# Gumstix_Overo.net
KiCad netlist of a schematic drawn in Altium Designer
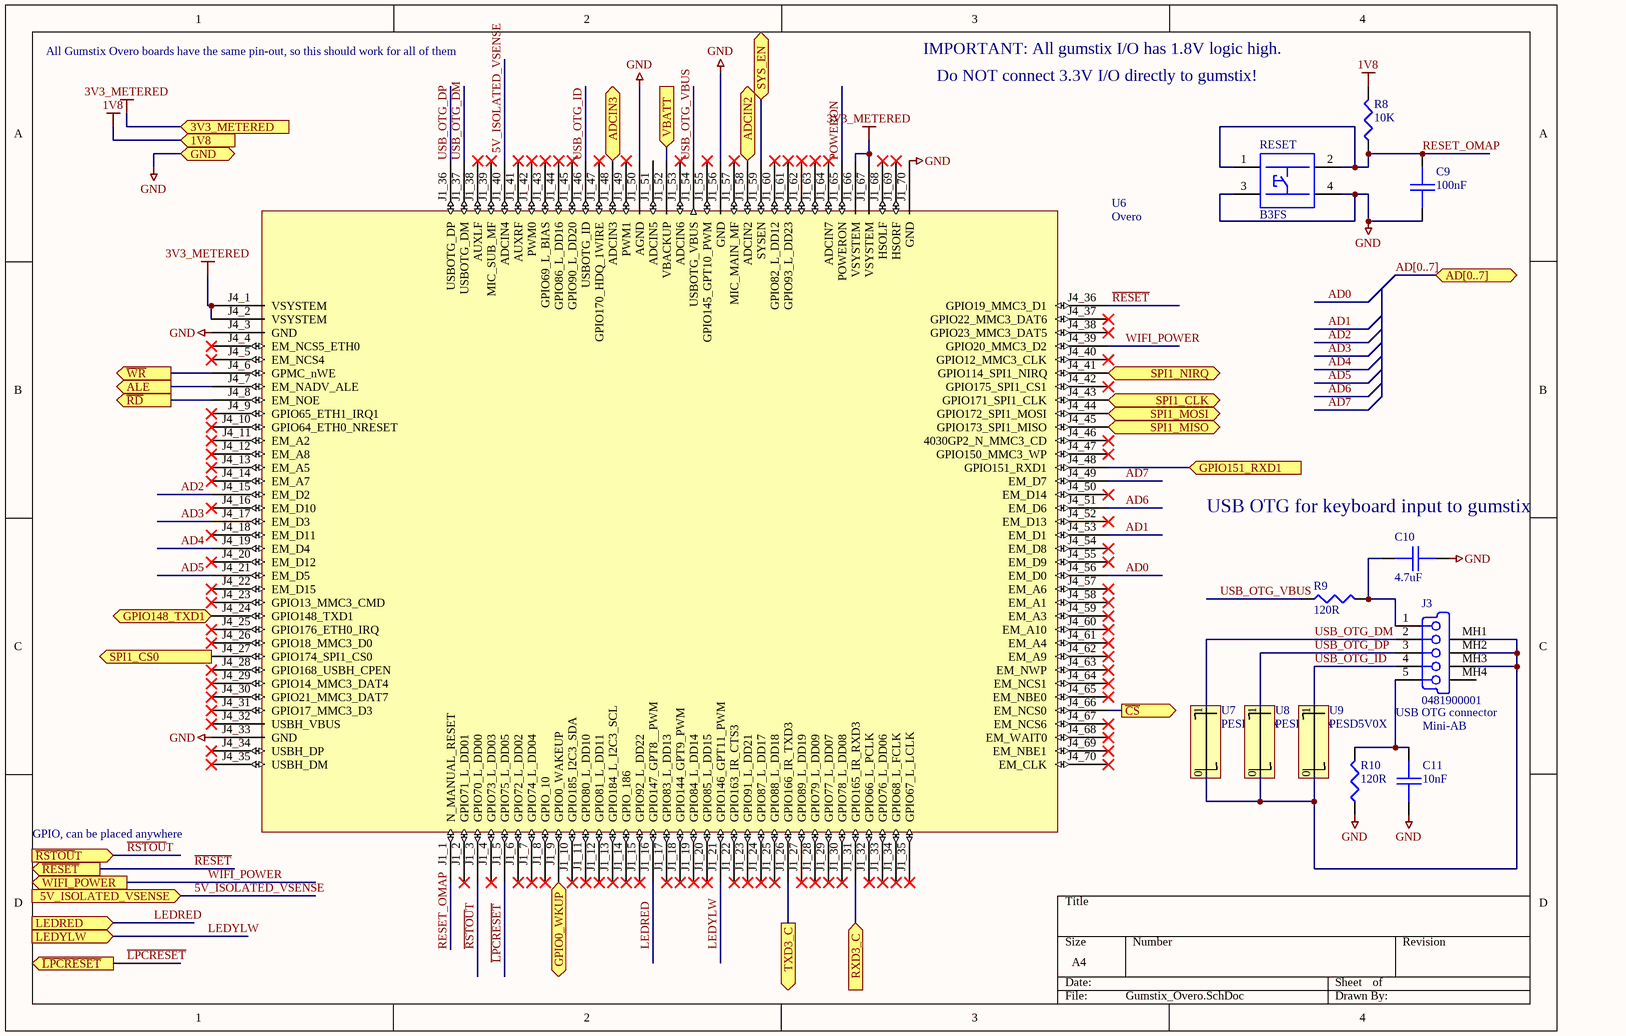
[diagram p0: Gumstix_Overo.SchDoc]

(export (version "E")
  (design (tool "Eeschema 10.0.6"))
  (components
    (comp (ref "C9")
      (value "100nF")
      (footprint "0603")
      (description "Capacitor")
      (libsource (lib "RCLDQ") (part "CAP"))
    )
    (comp (ref "C10")
      (value "4.7uF")
      (footprint "0603")
      (description "Capacitor")
      (libsource (lib "RCLDQ") (part "CAP"))
    )
    (comp (ref "C11")
      (value "10nF")
      (footprint "0603")
      (description "Capacitor")
      (libsource (lib "RCLDQ") (part "CAP"))
    )
    (comp (ref "J3")
      (value "0481900001")
      (footprint "MINI_USB_Molex")
      (fields (field (name "PUBLISHER") "Altium Limited"))
      (libsource (lib "Molex Serial Bus Mini USB") (part "0481900001"))
    )
    (comp (ref "R8")
      (value "10K")
      (footprint "0603")
      (description "Resistor")
      (libsource (lib "RCLDQ") (part "RES1"))
    )
    (comp (ref "R9")
      (value "120R")
      (footprint "0603")
      (description "Resistor")
      (libsource (lib "RCLDQ") (part "RES1"))
    )
    (comp (ref "R10")
      (value "120R")
      (footprint "0603")
      (description "Resistor")
      (libsource (lib "RCLDQ") (part "RES1"))
    )
    (comp (ref "RESET")
      (value "B3FS")
      (footprint "B3FS-1052")
      (description "SMD tactile switch")
      (libsource (lib "Miscellaneous") (part "B3FS"))
    )
    (comp (ref "U6")
      (value "Overo")
      (footprint "Overo-bare")
      (description "Gumstix Overo Motherboard")
      (libsource (lib "gumstix") (part "Overo"))
    )
    (comp (ref "U7")
      (value "PESD5V0X")
      (footprint "SOD323")
      (description "Ultra low capacitance bidirectional ESD protection diodes")
      (libsource (lib "gumstix") (part "PESD5V0X"))
    )
    (comp (ref "U8")
      (value "PESD5V0X")
      (footprint "SOD323")
      (description "Ultra low capacitance bidirectional ESD protection diodes")
      (libsource (lib "gumstix") (part "PESD5V0X"))
    )
    (comp (ref "U9")
      (value "PESD5V0X")
      (footprint "SOD323")
      (description "Ultra low capacitance bidirectional ESD protection diodes")
      (libsource (lib "gumstix") (part "PESD5V0X"))
    )
  )
  (nets
    (net (code "1") (name "/5V_ISOLATED_VSENSE") (class "Default")
      (node (ref "U6") (pin "J1_40") (pinfunction "ADCIN4_J1_40") (pintype "bidirectional"))
    )
    (net (code "2") (name "/AD0") (class "Default")
      (node (ref "U6") (pin "J4_56") (pinfunction "EM_D0_J4_56") (pintype "bidirectional"))
    )
    (net (code "3") (name "/AD1") (class "Default")
      (node (ref "U6") (pin "J4_53") (pinfunction "EM_D1_J4_53") (pintype "bidirectional"))
    )
    (net (code "4") (name "/AD2") (class "Default")
      (node (ref "U6") (pin "J4_15") (pinfunction "EM_D2_J4_15") (pintype "bidirectional"))
    )
    (net (code "5") (name "/AD3") (class "Default")
      (node (ref "U6") (pin "J4_17") (pinfunction "EM_D3_J4_17") (pintype "bidirectional"))
    )
    (net (code "6") (name "/AD4") (class "Default")
      (node (ref "U6") (pin "J4_19") (pinfunction "EM_D4_J4_19") (pintype "bidirectional"))
    )
    (net (code "7") (name "/AD5") (class "Default")
      (node (ref "U6") (pin "J4_21") (pinfunction "EM_D5_J4_21") (pintype "bidirectional"))
    )
    (net (code "8") (name "/AD6") (class "Default")
      (node (ref "U6") (pin "J4_51") (pinfunction "EM_D6_J4_51") (pintype "bidirectional"))
    )
    (net (code "9") (name "/AD7") (class "Default")
      (node (ref "U6") (pin "J4_49") (pinfunction "EM_D7_J4_49") (pintype "bidirectional"))
    )
    (net (code "10") (name "/ADCIN2") (class "Default")
      (node (ref "U6") (pin "J1_58") (pinfunction "ADCIN2_J1_58") (pintype "bidirectional"))
    )
    (net (code "11") (name "/ADCIN3") (class "Default")
      (node (ref "U6") (pin "J1_48") (pinfunction "ADCIN3_J1_48") (pintype "bidirectional"))
    )
    (net (code "13") (name "/ALE") (class "Default")
      (node (ref "U6") (pin "J4_7") (pinfunction "EM_NADV_ALE_J4_7") (pintype "bidirectional"))
    )
    (net (code "14") (name "/GPIO0_WKUP") (class "Default")
      (node (ref "U6") (pin "J1_9") (pinfunction "GPIO0_WAKEUP_J1_9") (pintype "bidirectional"))
    )
    (net (code "15") (name "/GPIO148_TXD1") (class "Default")
      (node (ref "U6") (pin "J4_24") (pinfunction "GPIO148_TXD1_J4_24") (pintype "bidirectional"))
    )
    (net (code "16") (name "/GPIO151_RXD1") (class "Default")
      (node (ref "U6") (pin "J4_48") (pinfunction "GPIO151_RXD1_J4_48") (pintype "bidirectional"))
    )
    (net (code "17") (name "/LEDRED") (class "Default")
      (node (ref "U6") (pin "J1_16") (pinfunction "GPIO147_GPT8__PWM_J1_16") (pintype "bidirectional"))
    )
    (net (code "18") (name "/LEDYLW") (class "Default")
      (node (ref "U6") (pin "J1_21") (pinfunction "GPIO146_GPT11_PWM_J1_21") (pintype "bidirectional"))
    )
    (net (code "19") (name "/POWERON") (class "Default")
      (node (ref "U6") (pin "J1_65") (pinfunction "POWERON_J1_65") (pintype "bidirectional"))
    )
    (net (code "20") (name "/RESET_OMAP") (class "Default")
      (node (ref "C9") (pin "1") (pinfunction "1_1") (pintype "passive"))
      (node (ref "R8") (pin "1") (pinfunction "1_1") (pintype "passive"))
      (node (ref "RESET") (pin "1") (pinfunction "A1_1") (pintype "passive"))
      (node (ref "RESET") (pin "2") (pinfunction "A2_2") (pintype "passive"))
      (node (ref "U6") (pin "J1_1") (pinfunction "N_MANUAL_RESET_J1_1") (pintype "bidirectional"))
    )
    (net (code "21") (name "/RXD3_C") (class "Default")
      (node (ref "U6") (pin "J1_31") (pinfunction "GPIO165_IR_RXD3_J1_31") (pintype "bidirectional"))
    )
    (net (code "22") (name "/SPI1_CLK") (class "Default")
      (node (ref "U6") (pin "J4_43") (pinfunction "GPIO171_SPI1_CLK_J4_43") (pintype "bidirectional"))
    )
    (net (code "23") (name "/SPI1_CS0") (class "Default")
      (node (ref "U6") (pin "J4_27") (pinfunction "GPIO174_SPI1_CS0_J4_27") (pintype "bidirectional"))
    )
    (net (code "24") (name "/SPI1_MISO") (class "Default")
      (node (ref "U6") (pin "J4_45") (pinfunction "GPIO173_SPI1_MISO_J4_45") (pintype "bidirectional"))
    )
    (net (code "25") (name "/SPI1_MOSI") (class "Default")
      (node (ref "U6") (pin "J4_44") (pinfunction "GPIO172_SPI1_MOSI_J4_44") (pintype "bidirectional"))
    )
    (net (code "26") (name "/SPI1_NIRQ") (class "Default")
      (node (ref "U6") (pin "J4_41") (pinfunction "GPIO114_SPI1_NIRQ_J4_41") (pintype "bidirectional"))
    )
    (net (code "27") (name "/SYS_EN") (class "Default")
      (node (ref "U6") (pin "J1_59") (pinfunction "SYSEN_J1_59") (pintype "bidirectional"))
    )
    (net (code "28") (name "/TXD3_C") (class "Default")
      (node (ref "U6") (pin "J1_26") (pinfunction "GPIO166_IR_TXD3_J1_26") (pintype "bidirectional"))
    )
    (net (code "29") (name "/USB_OTG_DM") (class "Default")
      (node (ref "J3") (pin "2") (pinfunction "D-_2") (pintype "passive"))
      (node (ref "U6") (pin "J1_37") (pinfunction "USBOTG_DM_J1_37") (pintype "bidirectional"))
      (node (ref "U7") (pin "1") (pintype "passive"))
    )
    (net (code "30") (name "/USB_OTG_DP") (class "Default")
      (node (ref "J3") (pin "3") (pinfunction "D+_3") (pintype "passive"))
      (node (ref "U6") (pin "J1_36") (pinfunction "USBOTG_DP_J1_36") (pintype "bidirectional"))
      (node (ref "U8") (pin "1") (pintype "passive"))
    )
    (net (code "31") (name "/USB_OTG_ID") (class "Default")
      (node (ref "J3") (pin "4") (pinfunction "NC_4") (pintype "passive"))
      (node (ref "U6") (pin "J1_46") (pinfunction "USBOTG_ID_J1_46") (pintype "bidirectional"))
      (node (ref "U9") (pin "1") (pintype "passive"))
    )
    (net (code "32") (name "/USB_OTG_VBUS") (class "Default")
      (node (ref "R9") (pin "1") (pinfunction "1_1") (pintype "passive"))
      (node (ref "U6") (pin "J1_54") (pinfunction "USBOTG_VBUS_J1_54") (pintype "output"))
    )
    (net (code "33") (name "/VBATT") (class "Default")
      (node (ref "U6") (pin "J1_52") (pinfunction "VBACKUP_J1_52") (pintype "power_in"))
    )
    (net (code "34") (name "/WIFI_POWER") (class "Default")
      (node (ref "U6") (pin "J4_39") (pinfunction "GPIO20_MMC3_D2_J4_39") (pintype "bidirectional"))
    )
    (net (code "35") (name "/~{CS}") (class "Default")
      (node (ref "U6") (pin "J4_66") (pinfunction "EM_NCS0_J4_66") (pintype "bidirectional"))
    )
    (net (code "36") (name "/~{LPCRESET}") (class "Default")
      (node (ref "U6") (pin "J1_5") (pinfunction "GPIO75_L_DD05_J1_5") (pintype "bidirectional"))
    )
    (net (code "37") (name "/~{RD}") (class "Default")
      (node (ref "U6") (pin "J4_8") (pinfunction "EM_NOE_J4_8") (pintype "bidirectional"))
    )
    (net (code "38") (name "/~{RESET}") (class "Default")
      (node (ref "U6") (pin "J4_36") (pinfunction "GPIO19_MMC3_D1_J4_36") (pintype "bidirectional"))
    )
    (net (code "39") (name "/~{RSTOU}T") (class "Default")
      (node (ref "U6") (pin "J1_3") (pinfunction "GPIO70_L_DD00_J1_3") (pintype "bidirectional"))
    )
    (net (code "40") (name "/~{WR}") (class "Default")
      (node (ref "U6") (pin "J4_6") (pinfunction "GPMC_nWE_J4_6") (pintype "bidirectional"))
    )
    (net (code "41") (name "1V8") (class "Default")
      (node (ref "R8") (pin "2") (pinfunction "2_2") (pintype "passive"))
    )
    (net (code "42") (name "3V3_METERED") (class "Default")
      (node (ref "U6") (pin "J1_66") (pinfunction "VSYSTEM_J1_66") (pintype "power_in"))
      (node (ref "U6") (pin "J1_67") (pinfunction "VSYSTEM_J1_67") (pintype "power_in"))
      (node (ref "U6") (pin "J4_1") (pinfunction "VSYSTEM_J4_1") (pintype "power_in"))
      (node (ref "U6") (pin "J4_2") (pinfunction "VSYSTEM_J4_2") (pintype "power_in"))
    )
    (net (code "43") (name "GND") (class "Default")
      (node (ref "C10") (pin "2") (pinfunction "2_2") (pintype "passive"))
      (node (ref "C11") (pin "2") (pinfunction "2_2") (pintype "passive"))
      (node (ref "C9") (pin "2") (pinfunction "2_2") (pintype "passive"))
      (node (ref "R10") (pin "1") (pinfunction "1_1") (pintype "passive"))
      (node (ref "RESET") (pin "3") (pinfunction "B2_3") (pintype "passive"))
      (node (ref "RESET") (pin "4") (pinfunction "B1_4") (pintype "passive"))
      (node (ref "U6") (pin "J1_50") (pinfunction "AGND_J1_50") (pintype "power_in"))
      (node (ref "U6") (pin "J1_56") (pinfunction "GND_J1_56") (pintype "power_in"))
      (node (ref "U6") (pin "J1_70") (pinfunction "GND_J1_70") (pintype "power_in"))
      (node (ref "U6") (pin "J4_3") (pinfunction "GND_J4_3") (pintype "power_in"))
      (node (ref "U6") (pin "J4_33") (pinfunction "GND_J4_33") (pintype "power_in"))
    )
    (net (code "44") (name "Net-(J3-GND)") (class "Default")
      (node (ref "C11") (pin "1") (pinfunction "1_1") (pintype "passive"))
      (node (ref "J3") (pin "5") (pinfunction "GND_5") (pintype "passive"))
      (node (ref "R10") (pin "2") (pinfunction "2_2") (pintype "passive"))
    )
    (net (code "45") (name "Net-(J3-Tab-PadMH1)") (class "Default")
      (node (ref "J3") (pin "MH1") (pinfunction "Tab_MH1") (pintype "passive"))
      (node (ref "J3") (pin "MH2") (pinfunction "Tab_MH2") (pintype "passive"))
      (node (ref "J3") (pin "MH3") (pinfunction "Tab_MH3") (pintype "passive"))
      (node (ref "U7") (pin "0") (pintype "passive"))
      (node (ref "U8") (pin "0") (pintype "passive"))
      (node (ref "U9") (pin "0") (pintype "passive"))
    )
    (net (code "46") (name "Net-(J3-V_BUS_(5V))") (class "Default")
      (node (ref "C10") (pin "1") (pinfunction "1_1") (pintype "passive"))
      (node (ref "J3") (pin "1") (pinfunction "V_BUS_(5V)_1") (pintype "passive"))
      (node (ref "R9") (pin "2") (pinfunction "2_2") (pintype "passive"))
    )
    (net (code "47") (name "unconnected-(J3-Tab-PadMH4)") (class "Default")
      (node (ref "J3") (pin "MH4") (pinfunction "Tab_MH4") (pintype "passive"))
    )
    (net (code "48") (name "unconnected-(U6-4030GP2_N_MMC3_CD-PadJ4_46)") (class "Default")
      (node (ref "U6") (pin "J4_46") (pinfunction "4030GP2_N_MMC3_CD_J4_46") (pintype "bidirectional+no_connect"))
    )
    (net (code "49") (name "unconnected-(U6-ADCIN5-PadJ1_51)") (class "Default")
      (node (ref "U6") (pin "J1_51") (pinfunction "ADCIN5_J1_51") (pintype "bidirectional"))
    )
    (net (code "50") (name "unconnected-(U6-ADCIN6-PadJ1_53)") (class "Default")
      (node (ref "U6") (pin "J1_53") (pinfunction "ADCIN6_J1_53") (pintype "bidirectional+no_connect"))
    )
    (net (code "51") (name "unconnected-(U6-ADCIN7-PadJ1_64)") (class "Default")
      (node (ref "U6") (pin "J1_64") (pinfunction "ADCIN7_J1_64") (pintype "bidirectional+no_connect"))
    )
    (net (code "52") (name "unconnected-(U6-AUXLF-PadJ1_38)") (class "Default")
      (node (ref "U6") (pin "J1_38") (pinfunction "AUXLF_J1_38") (pintype "bidirectional+no_connect"))
    )
    (net (code "53") (name "unconnected-(U6-AUXRF-PadJ1_41)") (class "Default")
      (node (ref "U6") (pin "J1_41") (pinfunction "AUXRF_J1_41") (pintype "bidirectional+no_connect"))
    )
    (net (code "54") (name "unconnected-(U6-EM_A1-PadJ4_58)") (class "Default")
      (node (ref "U6") (pin "J4_58") (pinfunction "EM_A1_J4_58") (pintype "bidirectional+no_connect"))
    )
    (net (code "55") (name "unconnected-(U6-EM_A2-PadJ4_11)") (class "Default")
      (node (ref "U6") (pin "J4_11") (pinfunction "EM_A2_J4_11") (pintype "bidirectional+no_connect"))
    )
    (net (code "56") (name "unconnected-(U6-EM_A3-PadJ4_59)") (class "Default")
      (node (ref "U6") (pin "J4_59") (pinfunction "EM_A3_J4_59") (pintype "bidirectional+no_connect"))
    )
    (net (code "57") (name "unconnected-(U6-EM_A4-PadJ4_61)") (class "Default")
      (node (ref "U6") (pin "J4_61") (pinfunction "EM_A4_J4_61") (pintype "bidirectional+no_connect"))
    )
    (net (code "58") (name "unconnected-(U6-EM_A5-PadJ4_13)") (class "Default")
      (node (ref "U6") (pin "J4_13") (pinfunction "EM_A5_J4_13") (pintype "bidirectional+no_connect"))
    )
    (net (code "59") (name "unconnected-(U6-EM_A6-PadJ4_57)") (class "Default")
      (node (ref "U6") (pin "J4_57") (pinfunction "EM_A6_J4_57") (pintype "bidirectional+no_connect"))
    )
    (net (code "60") (name "unconnected-(U6-EM_A7-PadJ4_14)") (class "Default")
      (node (ref "U6") (pin "J4_14") (pinfunction "EM_A7_J4_14") (pintype "bidirectional+no_connect"))
    )
    (net (code "61") (name "unconnected-(U6-EM_A8-PadJ4_12)") (class "Default")
      (node (ref "U6") (pin "J4_12") (pinfunction "EM_A8_J4_12") (pintype "bidirectional+no_connect"))
    )
    (net (code "62") (name "unconnected-(U6-EM_A9-PadJ4_62)") (class "Default")
      (node (ref "U6") (pin "J4_62") (pinfunction "EM_A9_J4_62") (pintype "bidirectional+no_connect"))
    )
    (net (code "63") (name "unconnected-(U6-EM_A10-PadJ4_60)") (class "Default")
      (node (ref "U6") (pin "J4_60") (pinfunction "EM_A10_J4_60") (pintype "bidirectional+no_connect"))
    )
    (net (code "64") (name "unconnected-(U6-EM_CLK-PadJ4_70)") (class "Default")
      (node (ref "U6") (pin "J4_70") (pinfunction "EM_CLK_J4_70") (pintype "bidirectional+no_connect"))
    )
    (net (code "65") (name "unconnected-(U6-EM_D8-PadJ4_54)") (class "Default")
      (node (ref "U6") (pin "J4_54") (pinfunction "EM_D8_J4_54") (pintype "bidirectional+no_connect"))
    )
    (net (code "66") (name "unconnected-(U6-EM_D9-PadJ4_55)") (class "Default")
      (node (ref "U6") (pin "J4_55") (pinfunction "EM_D9_J4_55") (pintype "bidirectional+no_connect"))
    )
    (net (code "67") (name "unconnected-(U6-EM_D10-PadJ4_16)") (class "Default")
      (node (ref "U6") (pin "J4_16") (pinfunction "EM_D10_J4_16") (pintype "bidirectional+no_connect"))
    )
    (net (code "68") (name "unconnected-(U6-EM_D11-PadJ4_18)") (class "Default")
      (node (ref "U6") (pin "J4_18") (pinfunction "EM_D11_J4_18") (pintype "bidirectional+no_connect"))
    )
    (net (code "69") (name "unconnected-(U6-EM_D12-PadJ4_20)") (class "Default")
      (node (ref "U6") (pin "J4_20") (pinfunction "EM_D12_J4_20") (pintype "bidirectional+no_connect"))
    )
    (net (code "70") (name "unconnected-(U6-EM_D13-PadJ4_52)") (class "Default")
      (node (ref "U6") (pin "J4_52") (pinfunction "EM_D13_J4_52") (pintype "bidirectional+no_connect"))
    )
    (net (code "71") (name "unconnected-(U6-EM_D14-PadJ4_50)") (class "Default")
      (node (ref "U6") (pin "J4_50") (pinfunction "EM_D14_J4_50") (pintype "bidirectional+no_connect"))
    )
    (net (code "72") (name "unconnected-(U6-EM_D15-PadJ4_22)") (class "Default")
      (node (ref "U6") (pin "J4_22") (pinfunction "EM_D15_J4_22") (pintype "bidirectional+no_connect"))
    )
    (net (code "73") (name "unconnected-(U6-EM_NBE0-PadJ4_65)") (class "Default")
      (node (ref "U6") (pin "J4_65") (pinfunction "EM_NBE0_J4_65") (pintype "bidirectional+no_connect"))
    )
    (net (code "74") (name "unconnected-(U6-EM_NBE1-PadJ4_69)") (class "Default")
      (node (ref "U6") (pin "J4_69") (pinfunction "EM_NBE1_J4_69") (pintype "bidirectional+no_connect"))
    )
    (net (code "75") (name "unconnected-(U6-EM_NCS1-PadJ4_64)") (class "Default")
      (node (ref "U6") (pin "J4_64") (pinfunction "EM_NCS1_J4_64") (pintype "bidirectional+no_connect"))
    )
    (net (code "76") (name "unconnected-(U6-EM_NCS4-PadJ4_5)") (class "Default")
      (node (ref "U6") (pin "J4_5") (pinfunction "EM_NCS4_J4_5") (pintype "bidirectional+no_connect"))
    )
    (net (code "77") (name "unconnected-(U6-EM_NCS5_ETH0-PadJ4_4)") (class "Default")
      (node (ref "U6") (pin "J4_4") (pinfunction "EM_NCS5_ETH0_J4_4") (pintype "bidirectional+no_connect"))
    )
    (net (code "78") (name "unconnected-(U6-EM_NCS6-PadJ4_67)") (class "Default")
      (node (ref "U6") (pin "J4_67") (pinfunction "EM_NCS6_J4_67") (pintype "bidirectional+no_connect"))
    )
    (net (code "79") (name "unconnected-(U6-EM_NWP-PadJ4_63)") (class "Default")
      (node (ref "U6") (pin "J4_63") (pinfunction "EM_NWP_J4_63") (pintype "bidirectional+no_connect"))
    )
    (net (code "80") (name "unconnected-(U6-EM_WAIT0-PadJ4_68)") (class "Default")
      (node (ref "U6") (pin "J4_68") (pinfunction "EM_WAIT0_J4_68") (pintype "bidirectional+no_connect"))
    )
    (net (code "81") (name "unconnected-(U6-GPIO12_MMC3_CLK-PadJ4_40)") (class "Default")
      (node (ref "U6") (pin "J4_40") (pinfunction "GPIO12_MMC3_CLK_J4_40") (pintype "bidirectional+no_connect"))
    )
    (net (code "82") (name "unconnected-(U6-GPIO13_MMC3_CMD-PadJ4_23)") (class "Default")
      (node (ref "U6") (pin "J4_23") (pinfunction "GPIO13_MMC3_CMD_J4_23") (pintype "bidirectional+no_connect"))
    )
    (net (code "83") (name "unconnected-(U6-GPIO14_MMC3_DAT4-PadJ4_29)") (class "Default")
      (node (ref "U6") (pin "J4_29") (pinfunction "GPIO14_MMC3_DAT4_J4_29") (pintype "bidirectional+no_connect"))
    )
    (net (code "84") (name "unconnected-(U6-GPIO17_MMC3_D3-PadJ4_31)") (class "Default")
      (node (ref "U6") (pin "J4_31") (pinfunction "GPIO17_MMC3_D3_J4_31") (pintype "bidirectional+no_connect"))
    )
    (net (code "85") (name "unconnected-(U6-GPIO18_MMC3_D0-PadJ4_26)") (class "Default")
      (node (ref "U6") (pin "J4_26") (pinfunction "GPIO18_MMC3_D0_J4_26") (pintype "bidirectional+no_connect"))
    )
    (net (code "86") (name "unconnected-(U6-GPIO21_MMC3_DAT7-PadJ4_30)") (class "Default")
      (node (ref "U6") (pin "J4_30") (pinfunction "GPIO21_MMC3_DAT7_J4_30") (pintype "bidirectional+no_connect"))
    )
    (net (code "87") (name "unconnected-(U6-GPIO22_MMC3_DAT6-PadJ4_37)") (class "Default")
      (node (ref "U6") (pin "J4_37") (pinfunction "GPIO22_MMC3_DAT6_J4_37") (pintype "bidirectional+no_connect"))
    )
    (net (code "88") (name "unconnected-(U6-GPIO23_MMC3_DAT5-PadJ4_38)") (class "Default")
      (node (ref "U6") (pin "J4_38") (pinfunction "GPIO23_MMC3_DAT5_J4_38") (pintype "bidirectional+no_connect"))
    )
    (net (code "89") (name "unconnected-(U6-GPIO64_ETH0_NRESET-PadJ4_10)") (class "Default")
      (node (ref "U6") (pin "J4_10") (pinfunction "GPIO64_ETH0_NRESET_J4_10") (pintype "bidirectional+no_connect"))
    )
    (net (code "90") (name "unconnected-(U6-GPIO65_ETH1_IRQ1-PadJ4_9)") (class "Default")
      (node (ref "U6") (pin "J4_9") (pinfunction "GPIO65_ETH1_IRQ1_J4_9") (pintype "bidirectional+no_connect"))
    )
    (net (code "91") (name "unconnected-(U6-GPIO66_L_PCLK-PadJ1_32)") (class "Default")
      (node (ref "U6") (pin "J1_32") (pinfunction "GPIO66_L_PCLK_J1_32") (pintype "bidirectional+no_connect"))
    )
    (net (code "92") (name "unconnected-(U6-GPIO67_L_LCLK-PadJ1_35)") (class "Default")
      (node (ref "U6") (pin "J1_35") (pinfunction "GPIO67_L_LCLK_J1_35") (pintype "bidirectional+no_connect"))
    )
    (net (code "93") (name "unconnected-(U6-GPIO68_L_FCLK-PadJ1_34)") (class "Default")
      (node (ref "U6") (pin "J1_34") (pinfunction "GPIO68_L_FCLK_J1_34") (pintype "bidirectional+no_connect"))
    )
    (net (code "94") (name "unconnected-(U6-GPIO69_L_BIAS-PadJ1_43)") (class "Default")
      (node (ref "U6") (pin "J1_43") (pinfunction "GPIO69_L_BIAS_J1_43") (pintype "bidirectional+no_connect"))
    )
    (net (code "95") (name "unconnected-(U6-GPIO71_L_DD01-PadJ1_2)") (class "Default")
      (node (ref "U6") (pin "J1_2") (pinfunction "GPIO71_L_DD01_J1_2") (pintype "bidirectional+no_connect"))
    )
    (net (code "96") (name "unconnected-(U6-GPIO72_L_DD02-PadJ1_6)") (class "Default")
      (node (ref "U6") (pin "J1_6") (pinfunction "GPIO72_L_DD02_J1_6") (pintype "bidirectional+no_connect"))
    )
    (net (code "97") (name "unconnected-(U6-GPIO73_L_DD03-PadJ1_4)") (class "Default")
      (node (ref "U6") (pin "J1_4") (pinfunction "GPIO73_L_DD03_J1_4") (pintype "bidirectional+no_connect"))
    )
    (net (code "98") (name "unconnected-(U6-GPIO74_L_DD04-PadJ1_7)") (class "Default")
      (node (ref "U6") (pin "J1_7") (pinfunction "GPIO74_L_DD04_J1_7") (pintype "bidirectional+no_connect"))
    )
    (net (code "99") (name "unconnected-(U6-GPIO76_L_DD06-PadJ1_33)") (class "Default")
      (node (ref "U6") (pin "J1_33") (pinfunction "GPIO76_L_DD06_J1_33") (pintype "bidirectional+no_connect"))
    )
    (net (code "100") (name "unconnected-(U6-GPIO77_L_DD07-PadJ1_29)") (class "Default")
      (node (ref "U6") (pin "J1_29") (pinfunction "GPIO77_L_DD07_J1_29") (pintype "bidirectional+no_connect"))
    )
    (net (code "101") (name "unconnected-(U6-GPIO78_L_DD08-PadJ1_30)") (class "Default")
      (node (ref "U6") (pin "J1_30") (pinfunction "GPIO78_L_DD08_J1_30") (pintype "bidirectional+no_connect"))
    )
    (net (code "102") (name "unconnected-(U6-GPIO79_L_DD09-PadJ1_28)") (class "Default")
      (node (ref "U6") (pin "J1_28") (pinfunction "GPIO79_L_DD09_J1_28") (pintype "bidirectional+no_connect"))
    )
    (net (code "103") (name "unconnected-(U6-GPIO80_L_DD10-PadJ1_11)") (class "Default")
      (node (ref "U6") (pin "J1_11") (pinfunction "GPIO80_L_DD10_J1_11") (pintype "bidirectional+no_connect"))
    )
    (net (code "104") (name "unconnected-(U6-GPIO81_L_DD11-PadJ1_12)") (class "Default")
      (node (ref "U6") (pin "J1_12") (pinfunction "GPIO81_L_DD11_J1_12") (pintype "bidirectional+no_connect"))
    )
    (net (code "105") (name "unconnected-(U6-GPIO82_L_DD12-PadJ1_60)") (class "Default")
      (node (ref "U6") (pin "J1_60") (pinfunction "GPIO82_L_DD12_J1_60") (pintype "bidirectional+no_connect"))
    )
    (net (code "106") (name "unconnected-(U6-GPIO83_L_DD13-PadJ1_17)") (class "Default")
      (node (ref "U6") (pin "J1_17") (pinfunction "GPIO83_L_DD13_J1_17") (pintype "bidirectional+no_connect"))
    )
    (net (code "107") (name "unconnected-(U6-GPIO84_L_DD14-PadJ1_19)") (class "Default")
      (node (ref "U6") (pin "J1_19") (pinfunction "GPIO84_L_DD14_J1_19") (pintype "bidirectional+no_connect"))
    )
    (net (code "108") (name "unconnected-(U6-GPIO85_L_DD15-PadJ1_20)") (class "Default")
      (node (ref "U6") (pin "J1_20") (pinfunction "GPIO85_L_DD15_J1_20") (pintype "bidirectional+no_connect"))
    )
    (net (code "109") (name "unconnected-(U6-GPIO86_L_DD16-PadJ1_44)") (class "Default")
      (node (ref "U6") (pin "J1_44") (pinfunction "GPIO86_L_DD16_J1_44") (pintype "bidirectional+no_connect"))
    )
    (net (code "110") (name "unconnected-(U6-GPIO87_L_DD17-PadJ1_24)") (class "Default")
      (node (ref "U6") (pin "J1_24") (pinfunction "GPIO87_L_DD17_J1_24") (pintype "bidirectional+no_connect"))
    )
    (net (code "111") (name "unconnected-(U6-GPIO88_L_DD18-PadJ1_25)") (class "Default")
      (node (ref "U6") (pin "J1_25") (pinfunction "GPIO88_L_DD18_J1_25") (pintype "bidirectional+no_connect"))
    )
    (net (code "112") (name "unconnected-(U6-GPIO89_L_DD19-PadJ1_27)") (class "Default")
      (node (ref "U6") (pin "J1_27") (pinfunction "GPIO89_L_DD19_J1_27") (pintype "bidirectional+no_connect"))
    )
    (net (code "113") (name "unconnected-(U6-GPIO90_L_DD20-PadJ1_45)") (class "Default")
      (node (ref "U6") (pin "J1_45") (pinfunction "GPIO90_L_DD20_J1_45") (pintype "bidirectional+no_connect"))
    )
    (net (code "114") (name "unconnected-(U6-GPIO91_L_DD21-PadJ1_23)") (class "Default")
      (node (ref "U6") (pin "J1_23") (pinfunction "GPIO91_L_DD21_J1_23") (pintype "bidirectional+no_connect"))
    )
    (net (code "115") (name "unconnected-(U6-GPIO92_L_DD22-PadJ1_15)") (class "Default")
      (node (ref "U6") (pin "J1_15") (pinfunction "GPIO92_L_DD22_J1_15") (pintype "bidirectional+no_connect"))
    )
    (net (code "116") (name "unconnected-(U6-GPIO93_L_DD23-PadJ1_61)") (class "Default")
      (node (ref "U6") (pin "J1_61") (pinfunction "GPIO93_L_DD23_J1_61") (pintype "bidirectional+no_connect"))
    )
    (net (code "117") (name "unconnected-(U6-GPIO144_GPT9_PWM-PadJ1_18)") (class "Default")
      (node (ref "U6") (pin "J1_18") (pinfunction "GPIO144_GPT9_PWM_J1_18") (pintype "bidirectional+no_connect"))
    )
    (net (code "118") (name "unconnected-(U6-GPIO145_GPT10_PWM-PadJ1_55)") (class "Default")
      (node (ref "U6") (pin "J1_55") (pinfunction "GPIO145_GPT10_PWM_J1_55") (pintype "bidirectional+no_connect"))
    )
    (net (code "119") (name "unconnected-(U6-GPIO150_MMC3_WP-PadJ4_47)") (class "Default")
      (node (ref "U6") (pin "J4_47") (pinfunction "GPIO150_MMC3_WP_J4_47") (pintype "bidirectional+no_connect"))
    )
    (net (code "120") (name "unconnected-(U6-GPIO163_IR_CTS3-PadJ1_22)") (class "Default")
      (node (ref "U6") (pin "J1_22") (pinfunction "GPIO163_IR_CTS3_J1_22") (pintype "bidirectional+no_connect"))
    )
    (net (code "121") (name "unconnected-(U6-GPIO168_USBH_CPEN-PadJ4_28)") (class "Default")
      (node (ref "U6") (pin "J4_28") (pinfunction "GPIO168_USBH_CPEN_J4_28") (pintype "bidirectional+no_connect"))
    )
    (net (code "122") (name "unconnected-(U6-GPIO170_HDQ_1WIRE-PadJ1_47)") (class "Default")
      (node (ref "U6") (pin "J1_47") (pinfunction "GPIO170_HDQ_1WIRE_J1_47") (pintype "bidirectional+no_connect"))
    )
    (net (code "123") (name "unconnected-(U6-GPIO175_SPI1_CS1-PadJ4_42)") (class "Default")
      (node (ref "U6") (pin "J4_42") (pinfunction "GPIO175_SPI1_CS1_J4_42") (pintype "bidirectional+no_connect"))
    )
    (net (code "124") (name "unconnected-(U6-GPIO176_ETH0_IRQ-PadJ4_25)") (class "Default")
      (node (ref "U6") (pin "J4_25") (pinfunction "GPIO176_ETH0_IRQ_J4_25") (pintype "bidirectional+no_connect"))
    )
    (net (code "125") (name "unconnected-(U6-GPIO184_L_I2C3_SCL-PadJ1_13)") (class "Default")
      (node (ref "U6") (pin "J1_13") (pinfunction "GPIO184_L_I2C3_SCL_J1_13") (pintype "bidirectional+no_connect"))
    )
    (net (code "126") (name "unconnected-(U6-GPIO185_I2C3_SDA-PadJ1_10)") (class "Default")
      (node (ref "U6") (pin "J1_10") (pinfunction "GPIO185_I2C3_SDA_J1_10") (pintype "bidirectional+no_connect"))
    )
    (net (code "127") (name "unconnected-(U6-GPIO_10-PadJ1_8)") (class "Default")
      (node (ref "U6") (pin "J1_8") (pinfunction "GPIO_10_J1_8") (pintype "bidirectional+no_connect"))
    )
    (net (code "128") (name "unconnected-(U6-GPIO_186-PadJ1_14)") (class "Default")
      (node (ref "U6") (pin "J1_14") (pinfunction "GPIO_186_J1_14") (pintype "bidirectional+no_connect"))
    )
    (net (code "129") (name "unconnected-(U6-HSOLF-PadJ1_68)") (class "Default")
      (node (ref "U6") (pin "J1_68") (pinfunction "HSOLF_J1_68") (pintype "bidirectional+no_connect"))
    )
    (net (code "130") (name "unconnected-(U6-HSORF-PadJ1_69)") (class "Default")
      (node (ref "U6") (pin "J1_69") (pinfunction "HSORF_J1_69") (pintype "bidirectional+no_connect"))
    )
    (net (code "131") (name "unconnected-(U6-MIC_MAIN_MF-PadJ1_57)") (class "Default")
      (node (ref "U6") (pin "J1_57") (pinfunction "MIC_MAIN_MF_J1_57") (pintype "bidirectional+no_connect"))
    )
    (net (code "132") (name "unconnected-(U6-MIC_SUB_MF-PadJ1_39)") (class "Default")
      (node (ref "U6") (pin "J1_39") (pinfunction "MIC_SUB_MF_J1_39") (pintype "bidirectional+no_connect"))
    )
    (net (code "133") (name "unconnected-(U6-PWM0-PadJ1_42)") (class "Default")
      (node (ref "U6") (pin "J1_42") (pinfunction "PWM0_J1_42") (pintype "bidirectional+no_connect"))
    )
    (net (code "134") (name "unconnected-(U6-PWM1-PadJ1_49)") (class "Default")
      (node (ref "U6") (pin "J1_49") (pinfunction "PWM1_J1_49") (pintype "bidirectional+no_connect"))
    )
    (net (code "135") (name "unconnected-(U6-PadJ1_62)") (class "Default")
      (node (ref "U6") (pin "J1_62") (pintype "bidirectional+no_connect"))
    )
    (net (code "136") (name "unconnected-(U6-PadJ1_63)") (class "Default")
      (node (ref "U6") (pin "J1_63") (pintype "bidirectional+no_connect"))
    )
    (net (code "137") (name "unconnected-(U6-USBH_DM-PadJ4_35)") (class "Default")
      (node (ref "U6") (pin "J4_35") (pinfunction "USBH_DM_J4_35") (pintype "bidirectional+no_connect"))
    )
    (net (code "138") (name "unconnected-(U6-USBH_DP-PadJ4_34)") (class "Default")
      (node (ref "U6") (pin "J4_34") (pinfunction "USBH_DP_J4_34") (pintype "bidirectional+no_connect"))
    )
    (net (code "139") (name "unconnected-(U6-USBH_VBUS-PadJ4_32)") (class "Default")
      (node (ref "U6") (pin "J4_32") (pinfunction "USBH_VBUS_J4_32") (pintype "power_in+no_connect"))
    )
  )
)
